# out.net
KiCad netlist of a schematic drawn in Altium Designer
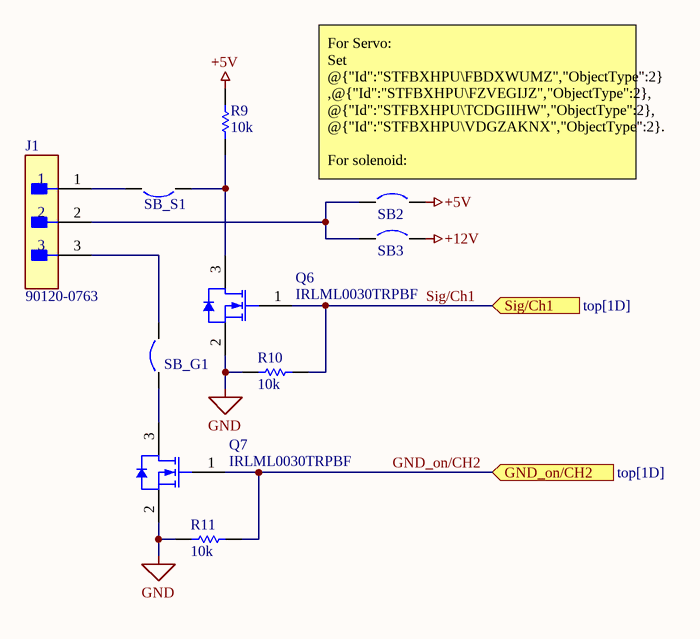
[diagram p0: out.SchDoc]

(export (version "E")
  (design (tool "Eeschema 10.0.6"))
  (components
    (comp (ref "J1")
      (value "90120-0763")
      (footprint "FP-90120-0763-MFG")
      (description "CONN HEADER VERT 3POS 2.54MM")
      (fields
        (field (name "MANUFACTURER") "Molex")
        (field (name "OCTOPART") "https://octopart.com/90120-0763-molex-655433")
      )
      (libsource (lib "Altium Content Vault") (part "0d3f023dd272f625e17a2be33dea85f"))
    )
    (comp (ref "Q6")
      (value "IRLML0030TRPBF")
      (footprint "INTR-SOT-23-3_V")
      (description "HEXFET(R) Power MOSFET, 1.3 W, 4.4 ns, -55 to 150 degC, 3-Pin SOT-23, RoHS, Tape and Reel")
      (fields (field (name "MANUFACTURER") "International Rectifier"))
      (libsource (lib "Altium Content Vault") (part "NEMOS-GSD-3"))
    )
    (comp (ref "Q7")
      (value "IRLML0030TRPBF")
      (footprint "INTR-SOT-23-3_V")
      (description "HEXFET(R) Power MOSFET, 1.3 W, 4.4 ns, -55 to 150 degC, 3-Pin SOT-23, RoHS, Tape and Reel")
      (fields (field (name "MANUFACTURER") "International Rectifier"))
      (libsource (lib "Altium Content Vault") (part "NEMOS-GSD-3"))
    )
    (comp (ref "R9")
      (value "10k")
      (footprint "RESC1609X55X30NL15T15")
      (description "Chip Resistor, 10 KOhm, +/- 1%, 0.1 W, -55 to 155 degC, 0603 (1608 Metric), RoHS, Tape and Reel")
      (fields (field (name "TOLERANCE") "1%") (field (name "MANUFACTURER") "Panasonic"))
      (libsource (lib "Altium Content Vault") (part "RES-2"))
    )
    (comp (ref "R10")
      (value "10k")
      (footprint "RESC1609X55X30NL15T15")
      (description "Chip Resistor, 10 KOhm, +/- 1%, 0.1 W, -55 to 155 degC, 0603 (1608 Metric), RoHS, Tape and Reel")
      (fields (field (name "TOLERANCE") "1%") (field (name "MANUFACTURER") "Panasonic"))
      (libsource (lib "Altium Content Vault") (part "RES-2"))
    )
    (comp (ref "R11")
      (value "10k")
      (footprint "RESC1609X55X30NL15T15")
      (description "Chip Resistor, 10 KOhm, +/- 1%, 0.1 W, -55 to 155 degC, 0603 (1608 Metric), RoHS, Tape and Reel")
      (fields (field (name "TOLERANCE") "1%") (field (name "MANUFACTURER") "Panasonic"))
      (libsource (lib "Altium Content Vault") (part "RES-2"))
    )
    (comp (ref "SB2")
      (value "~")
      (footprint "JP_SMD")
      (description "Circuit Breaker")
      (fields (field (name "PUBLISHER") "Altium Limited"))
      (libsource (lib "test_adc") (part "Circuit Breaker"))
    )
    (comp (ref "SB3")
      (value "~")
      (footprint "JP_SMD")
      (description "Circuit Breaker")
      (fields (field (name "PUBLISHER") "Altium Limited"))
      (libsource (lib "test_adc") (part "Circuit Breaker"))
    )
    (comp (ref "SB_G1")
      (value "~")
      (footprint "JP_SMD")
      (description "Circuit Breaker")
      (fields (field (name "PUBLISHER") "Altium Limited"))
      (libsource (lib "test_adc") (part "Circuit Breaker"))
    )
    (comp (ref "SB_S1")
      (value "~")
      (footprint "JP_SMD")
      (description "Circuit Breaker")
      (fields (field (name "PUBLISHER") "Altium Limited"))
      (libsource (lib "test_adc") (part "Circuit Breaker"))
    )
  )
  (nets
    (net (code "1") (name "+5V") (class "Default")
      (node (ref "R9") (pin "1") (pinfunction "1_1") (pintype "passive"))
      (node (ref "SB2") (pin "2") (pinfunction "2_2") (pintype "passive"))
    )
    (net (code "2") (name "+12V") (class "Default")
      (node (ref "SB3") (pin "2") (pinfunction "2_2") (pintype "passive"))
    )
    (net (code "3") (name "/GND_on{slash}CH2") (class "Default")
      (node (ref "Q7") (pin "1") (pinfunction "G_1") (pintype "passive"))
      (node (ref "R11") (pin "1") (pinfunction "1_1") (pintype "passive"))
    )
    (net (code "4") (name "/Sig{slash}Ch1") (class "Default")
      (node (ref "Q6") (pin "1") (pinfunction "G_1") (pintype "passive"))
      (node (ref "R10") (pin "1") (pinfunction "1_1") (pintype "passive"))
    )
    (net (code "5") (name "GND") (class "Default")
      (node (ref "Q6") (pin "2") (pinfunction "S_2") (pintype "passive"))
      (node (ref "Q7") (pin "2") (pinfunction "S_2") (pintype "passive"))
      (node (ref "R10") (pin "2") (pinfunction "2_2") (pintype "passive"))
      (node (ref "R11") (pin "2") (pinfunction "2_2") (pintype "passive"))
    )
    (net (code "6") (name "Net-(J1-Pad1)") (class "Default")
      (node (ref "J1") (pin "1") (pinfunction "1_1") (pintype "passive"))
      (node (ref "SB_S1") (pin "2") (pinfunction "2_2") (pintype "passive"))
    )
    (net (code "7") (name "Net-(J1-Pad2)") (class "Default")
      (node (ref "J1") (pin "2") (pinfunction "2_2") (pintype "passive"))
      (node (ref "SB2") (pin "1") (pinfunction "1_1") (pintype "passive"))
      (node (ref "SB3") (pin "1") (pinfunction "1_1") (pintype "passive"))
    )
    (net (code "8") (name "Net-(J1-Pad3)") (class "Default")
      (node (ref "J1") (pin "3") (pinfunction "3_3") (pintype "passive"))
      (node (ref "SB_G1") (pin "2") (pinfunction "2_2") (pintype "passive"))
    )
    (net (code "9") (name "Net-(Q6-D)") (class "Default")
      (node (ref "Q6") (pin "3") (pinfunction "D_3") (pintype "passive"))
      (node (ref "R9") (pin "2") (pinfunction "2_2") (pintype "passive"))
      (node (ref "SB_S1") (pin "1") (pinfunction "1_1") (pintype "passive"))
    )
    (net (code "10") (name "Net-(Q7-D)") (class "Default")
      (node (ref "Q7") (pin "3") (pinfunction "D_3") (pintype "passive"))
      (node (ref "SB_G1") (pin "1") (pinfunction "1_1") (pintype "passive"))
    )
  )
)
